# Downey.net
KiCad netlist of a schematic drawn in EAGLE
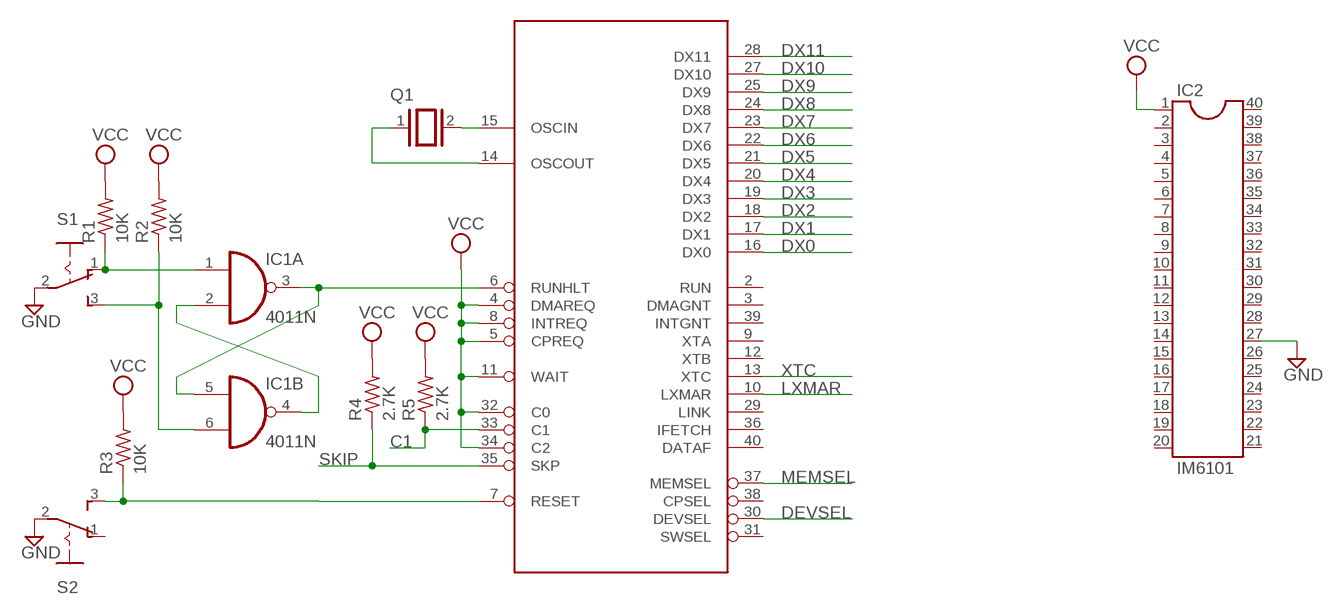
[diagram p0: schematic, sheet 1]

(export (version "E")
  (design (tool "Eeschema 10.0.6"))
  (components
    (comp (ref "IC1")
      (value "4011N")
      (footprint "eagle-import:DIL14")
      (libsource (lib "eagle-import") (part "4011N"))
    )
    (comp (ref "IC2")
      (value "IM6101")
      (footprint "eagle-import:DIL40")
      (libsource (lib "eagle-import") (part "DIL40"))
    )
    (comp (ref "Q1")
      (value "XTAL/S")
      (footprint "eagle-import:QS")
      (libsource (lib "eagle-import") (part "XTAL/S"))
    )
    (comp (ref "R1")
      (value "10K")
      (footprint "eagle-import:0207_10")
      (libsource (lib "eagle-import") (part "R-US_0207/10"))
    )
    (comp (ref "R2")
      (value "10K")
      (footprint "eagle-import:0207_10")
      (libsource (lib "eagle-import") (part "R-US_0207/10"))
    )
    (comp (ref "R3")
      (value "10K")
      (footprint "eagle-import:0207_10")
      (libsource (lib "eagle-import") (part "R-US_0207/10"))
    )
    (comp (ref "R4")
      (value "2.7K")
      (footprint "eagle-import:0207_10")
      (libsource (lib "eagle-import") (part "R-US_0207/10"))
    )
    (comp (ref "R5")
      (value "2.7K")
      (footprint "eagle-import:0207_10")
      (libsource (lib "eagle-import") (part "R-US_0207/10"))
    )
    (comp (ref "S1")
      (value "255SB")
      (footprint "eagle-import:255SB")
      (libsource (lib "eagle-import") (part "255SB"))
    )
    (comp (ref "S2")
      (value "255SB")
      (footprint "eagle-import:255SB")
      (libsource (lib "eagle-import") (part "255SB"))
    )
    (comp (ref "U$1")
      (value "IM6100")
      (footprint "eagle-import:DIL40")
      (libsource (lib "eagle-import") (part "IM6100"))
    )
  )
  (nets
    (net (code "1") (name "/C1") (class "Default")
      (node (ref "R5") (pin "1") (pinfunction "1_1") (pintype "passive"))
      (node (ref "U$1") (pin "33") (pinfunction "C1_33") (pintype "input"))
    )
    (net (code "2") (name "/DEVSEL") (class "Default")
      (node (ref "U$1") (pin "30") (pinfunction "DEVSEL_30") (pintype "output"))
    )
    (net (code "3") (name "/DX0") (class "Default")
      (node (ref "U$1") (pin "16") (pinfunction "DX0_16") (pintype "bidirectional"))
    )
    (net (code "4") (name "/DX1") (class "Default")
      (node (ref "U$1") (pin "17") (pinfunction "DX1_17") (pintype "bidirectional"))
    )
    (net (code "5") (name "/DX2") (class "Default")
      (node (ref "U$1") (pin "18") (pinfunction "DX2_18") (pintype "bidirectional"))
    )
    (net (code "6") (name "/DX3") (class "Default")
      (node (ref "U$1") (pin "19") (pinfunction "DX3_19") (pintype "bidirectional"))
    )
    (net (code "7") (name "/DX4") (class "Default")
      (node (ref "U$1") (pin "20") (pinfunction "DX4_20") (pintype "bidirectional"))
    )
    (net (code "8") (name "/DX5") (class "Default")
      (node (ref "U$1") (pin "21") (pinfunction "DX5_21") (pintype "bidirectional"))
    )
    (net (code "9") (name "/DX6") (class "Default")
      (node (ref "U$1") (pin "22") (pinfunction "DX6_22") (pintype "bidirectional"))
    )
    (net (code "10") (name "/DX7") (class "Default")
      (node (ref "U$1") (pin "23") (pinfunction "DX7_23") (pintype "bidirectional"))
    )
    (net (code "11") (name "/DX8") (class "Default")
      (node (ref "U$1") (pin "24") (pinfunction "DX8_24") (pintype "bidirectional"))
    )
    (net (code "12") (name "/DX9") (class "Default")
      (node (ref "U$1") (pin "25") (pinfunction "DX9_25") (pintype "bidirectional"))
    )
    (net (code "13") (name "/DX10") (class "Default")
      (node (ref "U$1") (pin "27") (pinfunction "DX10_27") (pintype "bidirectional"))
    )
    (net (code "14") (name "/DX11") (class "Default")
      (node (ref "U$1") (pin "28") (pinfunction "DX11_28") (pintype "bidirectional"))
    )
    (net (code "15") (name "/LXMAR") (class "Default")
      (node (ref "U$1") (pin "10") (pinfunction "LXMAR_10") (pintype "output"))
    )
    (net (code "16") (name "/MEMSEL") (class "Default")
      (node (ref "U$1") (pin "37") (pinfunction "MEMSEL_37") (pintype "output"))
    )
    (net (code "17") (name "/SKIP") (class "Default")
      (node (ref "R4") (pin "1") (pinfunction "1_1") (pintype "passive"))
      (node (ref "U$1") (pin "35") (pinfunction "SKP_35") (pintype "input"))
    )
    (net (code "18") (name "/XTC") (class "Default")
      (node (ref "U$1") (pin "13") (pinfunction "XTC_13") (pintype "output"))
    )
    (net (code "19") (name "GND") (class "Default")
      (node (ref "IC2") (pin "27") (pinfunction "27_27") (pintype "passive"))
      (node (ref "S1") (pin "2") (pinfunction "P_2") (pintype "passive"))
      (node (ref "S2") (pin "2") (pinfunction "P_2") (pintype "passive"))
    )
    (net (code "20") (name "Net-(IC1A-I0)") (class "Default")
      (node (ref "IC1") (pin "1") (pinfunction "I0_1") (pintype "input"))
      (node (ref "R1") (pin "1") (pinfunction "1_1") (pintype "passive"))
      (node (ref "S1") (pin "1") (pinfunction "O_1") (pintype "passive"))
    )
    (net (code "21") (name "Net-(IC1A-I1)") (class "Default")
      (node (ref "IC1") (pin "2") (pinfunction "I1_2") (pintype "input"))
      (node (ref "IC1") (pin "4") (pinfunction "O_4") (pintype "output"))
    )
    (net (code "22") (name "Net-(IC1A-O)") (class "Default")
      (node (ref "IC1") (pin "3") (pinfunction "O_3") (pintype "output"))
      (node (ref "IC1") (pin "5") (pinfunction "I0_5") (pintype "input"))
      (node (ref "U$1") (pin "6") (pinfunction "RUNHLT_6") (pintype "input"))
    )
    (net (code "23") (name "Net-(IC1B-I1)") (class "Default")
      (node (ref "IC1") (pin "6") (pinfunction "I1_6") (pintype "input"))
      (node (ref "R2") (pin "1") (pinfunction "1_1") (pintype "passive"))
      (node (ref "S1") (pin "3") (pinfunction "S_3") (pintype "passive"))
    )
    (net (code "24") (name "Net-(S2-S)") (class "Default")
      (node (ref "R3") (pin "1") (pinfunction "1_1") (pintype "passive"))
      (node (ref "S2") (pin "3") (pinfunction "S_3") (pintype "passive"))
      (node (ref "U$1") (pin "7") (pinfunction "RESET_7") (pintype "input"))
    )
    (net (code "25") (name "Net-(U$1A-OSCIN)") (class "Default")
      (node (ref "Q1") (pin "2") (pinfunction "2_2") (pintype "passive"))
      (node (ref "U$1") (pin "15") (pinfunction "OSCIN_15") (pintype "input"))
    )
    (net (code "26") (name "Net-(U$1A-OSCOUT)") (class "Default")
      (node (ref "Q1") (pin "1") (pinfunction "1_1") (pintype "passive"))
      (node (ref "U$1") (pin "14") (pinfunction "OSCOUT_14") (pintype "output"))
    )
    (net (code "27") (name "VCC") (class "Default")
      (node (ref "IC2") (pin "1") (pinfunction "1_1") (pintype "passive"))
      (node (ref "R1") (pin "2") (pinfunction "2_2") (pintype "passive"))
      (node (ref "R2") (pin "2") (pinfunction "2_2") (pintype "passive"))
      (node (ref "R3") (pin "2") (pinfunction "2_2") (pintype "passive"))
      (node (ref "R4") (pin "2") (pinfunction "2_2") (pintype "passive"))
      (node (ref "R5") (pin "2") (pinfunction "2_2") (pintype "passive"))
      (node (ref "U$1") (pin "11") (pinfunction "WAIT_11") (pintype "input"))
      (node (ref "U$1") (pin "32") (pinfunction "C0_32") (pintype "input"))
      (node (ref "U$1") (pin "34") (pinfunction "C2_34") (pintype "input"))
      (node (ref "U$1") (pin "4") (pinfunction "DMAREQ_4") (pintype "input"))
      (node (ref "U$1") (pin "5") (pinfunction "CPREQ_5") (pintype "input"))
      (node (ref "U$1") (pin "8") (pinfunction "INTREQ_8") (pintype "input"))
    )
    (net (code "28") (name "unconnected-(IC2-Pad2)") (class "Default")
      (node (ref "IC2") (pin "2") (pinfunction "2_2") (pintype "passive"))
    )
    (net (code "29") (name "unconnected-(IC2-Pad3)") (class "Default")
      (node (ref "IC2") (pin "3") (pinfunction "3_3") (pintype "passive"))
    )
    (net (code "30") (name "unconnected-(IC2-Pad4)") (class "Default")
      (node (ref "IC2") (pin "4") (pinfunction "4_4") (pintype "passive"))
    )
    (net (code "31") (name "unconnected-(IC2-Pad5)") (class "Default")
      (node (ref "IC2") (pin "5") (pinfunction "5_5") (pintype "passive"))
    )
    (net (code "32") (name "unconnected-(IC2-Pad6)") (class "Default")
      (node (ref "IC2") (pin "6") (pinfunction "6_6") (pintype "passive"))
    )
    (net (code "33") (name "unconnected-(IC2-Pad7)") (class "Default")
      (node (ref "IC2") (pin "7") (pinfunction "7_7") (pintype "passive"))
    )
    (net (code "34") (name "unconnected-(IC2-Pad8)") (class "Default")
      (node (ref "IC2") (pin "8") (pinfunction "8_8") (pintype "passive"))
    )
    (net (code "35") (name "unconnected-(IC2-Pad9)") (class "Default")
      (node (ref "IC2") (pin "9") (pinfunction "9_9") (pintype "passive"))
    )
    (net (code "36") (name "unconnected-(IC2-Pad10)") (class "Default")
      (node (ref "IC2") (pin "10") (pinfunction "10_10") (pintype "passive"))
    )
    (net (code "37") (name "unconnected-(IC2-Pad11)") (class "Default")
      (node (ref "IC2") (pin "11") (pinfunction "11_11") (pintype "passive"))
    )
    (net (code "38") (name "unconnected-(IC2-Pad12)") (class "Default")
      (node (ref "IC2") (pin "12") (pinfunction "12_12") (pintype "passive"))
    )
    (net (code "39") (name "unconnected-(IC2-Pad13)") (class "Default")
      (node (ref "IC2") (pin "13") (pinfunction "13_13") (pintype "passive"))
    )
    (net (code "40") (name "unconnected-(IC2-Pad14)") (class "Default")
      (node (ref "IC2") (pin "14") (pinfunction "14_14") (pintype "passive"))
    )
    (net (code "41") (name "unconnected-(IC2-Pad15)") (class "Default")
      (node (ref "IC2") (pin "15") (pinfunction "15_15") (pintype "passive"))
    )
    (net (code "42") (name "unconnected-(IC2-Pad16)") (class "Default")
      (node (ref "IC2") (pin "16") (pinfunction "16_16") (pintype "passive"))
    )
    (net (code "43") (name "unconnected-(IC2-Pad17)") (class "Default")
      (node (ref "IC2") (pin "17") (pinfunction "17_17") (pintype "passive"))
    )
    (net (code "44") (name "unconnected-(IC2-Pad18)") (class "Default")
      (node (ref "IC2") (pin "18") (pinfunction "18_18") (pintype "passive"))
    )
    (net (code "45") (name "unconnected-(IC2-Pad19)") (class "Default")
      (node (ref "IC2") (pin "19") (pinfunction "19_19") (pintype "passive"))
    )
    (net (code "46") (name "unconnected-(IC2-Pad20)") (class "Default")
      (node (ref "IC2") (pin "20") (pinfunction "20_20") (pintype "passive"))
    )
    (net (code "47") (name "unconnected-(IC2-Pad21)") (class "Default")
      (node (ref "IC2") (pin "21") (pinfunction "21_21") (pintype "passive"))
    )
    (net (code "48") (name "unconnected-(IC2-Pad22)") (class "Default")
      (node (ref "IC2") (pin "22") (pinfunction "22_22") (pintype "passive"))
    )
    (net (code "49") (name "unconnected-(IC2-Pad23)") (class "Default")
      (node (ref "IC2") (pin "23") (pinfunction "23_23") (pintype "passive"))
    )
    (net (code "50") (name "unconnected-(IC2-Pad24)") (class "Default")
      (node (ref "IC2") (pin "24") (pinfunction "24_24") (pintype "passive"))
    )
    (net (code "51") (name "unconnected-(IC2-Pad25)") (class "Default")
      (node (ref "IC2") (pin "25") (pinfunction "25_25") (pintype "passive"))
    )
    (net (code "52") (name "unconnected-(IC2-Pad26)") (class "Default")
      (node (ref "IC2") (pin "26") (pinfunction "26_26") (pintype "passive"))
    )
    (net (code "53") (name "unconnected-(IC2-Pad28)") (class "Default")
      (node (ref "IC2") (pin "28") (pinfunction "28_28") (pintype "passive"))
    )
    (net (code "54") (name "unconnected-(IC2-Pad29)") (class "Default")
      (node (ref "IC2") (pin "29") (pinfunction "29_29") (pintype "passive"))
    )
    (net (code "55") (name "unconnected-(IC2-Pad30)") (class "Default")
      (node (ref "IC2") (pin "30") (pinfunction "30_30") (pintype "passive"))
    )
    (net (code "56") (name "unconnected-(IC2-Pad31)") (class "Default")
      (node (ref "IC2") (pin "31") (pinfunction "31_31") (pintype "passive"))
    )
    (net (code "57") (name "unconnected-(IC2-Pad32)") (class "Default")
      (node (ref "IC2") (pin "32") (pinfunction "32_32") (pintype "passive"))
    )
    (net (code "58") (name "unconnected-(IC2-Pad33)") (class "Default")
      (node (ref "IC2") (pin "33") (pinfunction "33_33") (pintype "passive"))
    )
    (net (code "59") (name "unconnected-(IC2-Pad34)") (class "Default")
      (node (ref "IC2") (pin "34") (pinfunction "34_34") (pintype "passive"))
    )
    (net (code "60") (name "unconnected-(IC2-Pad35)") (class "Default")
      (node (ref "IC2") (pin "35") (pinfunction "35_35") (pintype "passive"))
    )
    (net (code "61") (name "unconnected-(IC2-Pad36)") (class "Default")
      (node (ref "IC2") (pin "36") (pinfunction "36_36") (pintype "passive"))
    )
    (net (code "62") (name "unconnected-(IC2-Pad37)") (class "Default")
      (node (ref "IC2") (pin "37") (pinfunction "37_37") (pintype "passive"))
    )
    (net (code "63") (name "unconnected-(IC2-Pad38)") (class "Default")
      (node (ref "IC2") (pin "38") (pinfunction "38_38") (pintype "passive"))
    )
    (net (code "64") (name "unconnected-(IC2-Pad39)") (class "Default")
      (node (ref "IC2") (pin "39") (pinfunction "39_39") (pintype "passive"))
    )
    (net (code "65") (name "unconnected-(IC2-Pad40)") (class "Default")
      (node (ref "IC2") (pin "40") (pinfunction "40_40") (pintype "passive"))
    )
    (net (code "66") (name "unconnected-(S2-O-Pad1)") (class "Default")
      (node (ref "S2") (pin "1") (pinfunction "O_1") (pintype "passive"))
    )
    (net (code "67") (name "unconnected-(U$1A-CPSEL-Pad38)") (class "Default")
      (node (ref "U$1") (pin "38") (pinfunction "CPSEL_38") (pintype "output"))
    )
    (net (code "68") (name "unconnected-(U$1A-DATAF-Pad40)") (class "Default")
      (node (ref "U$1") (pin "40") (pinfunction "DATAF_40") (pintype "output"))
    )
    (net (code "69") (name "unconnected-(U$1A-DMAGNT-Pad3)") (class "Default")
      (node (ref "U$1") (pin "3") (pinfunction "DMAGNT_3") (pintype "output"))
    )
    (net (code "70") (name "unconnected-(U$1A-IFETCH-Pad36)") (class "Default")
      (node (ref "U$1") (pin "36") (pinfunction "IFETCH_36") (pintype "output"))
    )
    (net (code "71") (name "unconnected-(U$1A-INTGNT-Pad39)") (class "Default")
      (node (ref "U$1") (pin "39") (pinfunction "INTGNT_39") (pintype "output"))
    )
    (net (code "72") (name "unconnected-(U$1A-LINK-Pad29)") (class "Default")
      (node (ref "U$1") (pin "29") (pinfunction "LINK_29") (pintype "output"))
    )
    (net (code "73") (name "unconnected-(U$1A-RUN-Pad2)") (class "Default")
      (node (ref "U$1") (pin "2") (pinfunction "RUN_2") (pintype "output"))
    )
    (net (code "74") (name "unconnected-(U$1A-SWSEL-Pad31)") (class "Default")
      (node (ref "U$1") (pin "31") (pinfunction "SWSEL_31") (pintype "output"))
    )
    (net (code "75") (name "unconnected-(U$1A-XTA-Pad9)") (class "Default")
      (node (ref "U$1") (pin "9") (pinfunction "XTA_9") (pintype "output"))
    )
    (net (code "76") (name "unconnected-(U$1A-XTB-Pad12)") (class "Default")
      (node (ref "U$1") (pin "12") (pinfunction "XTB_12") (pintype "output"))
    )
  )
)
